# Buttons.net
KiCad netlist of a schematic drawn in Altium Designer
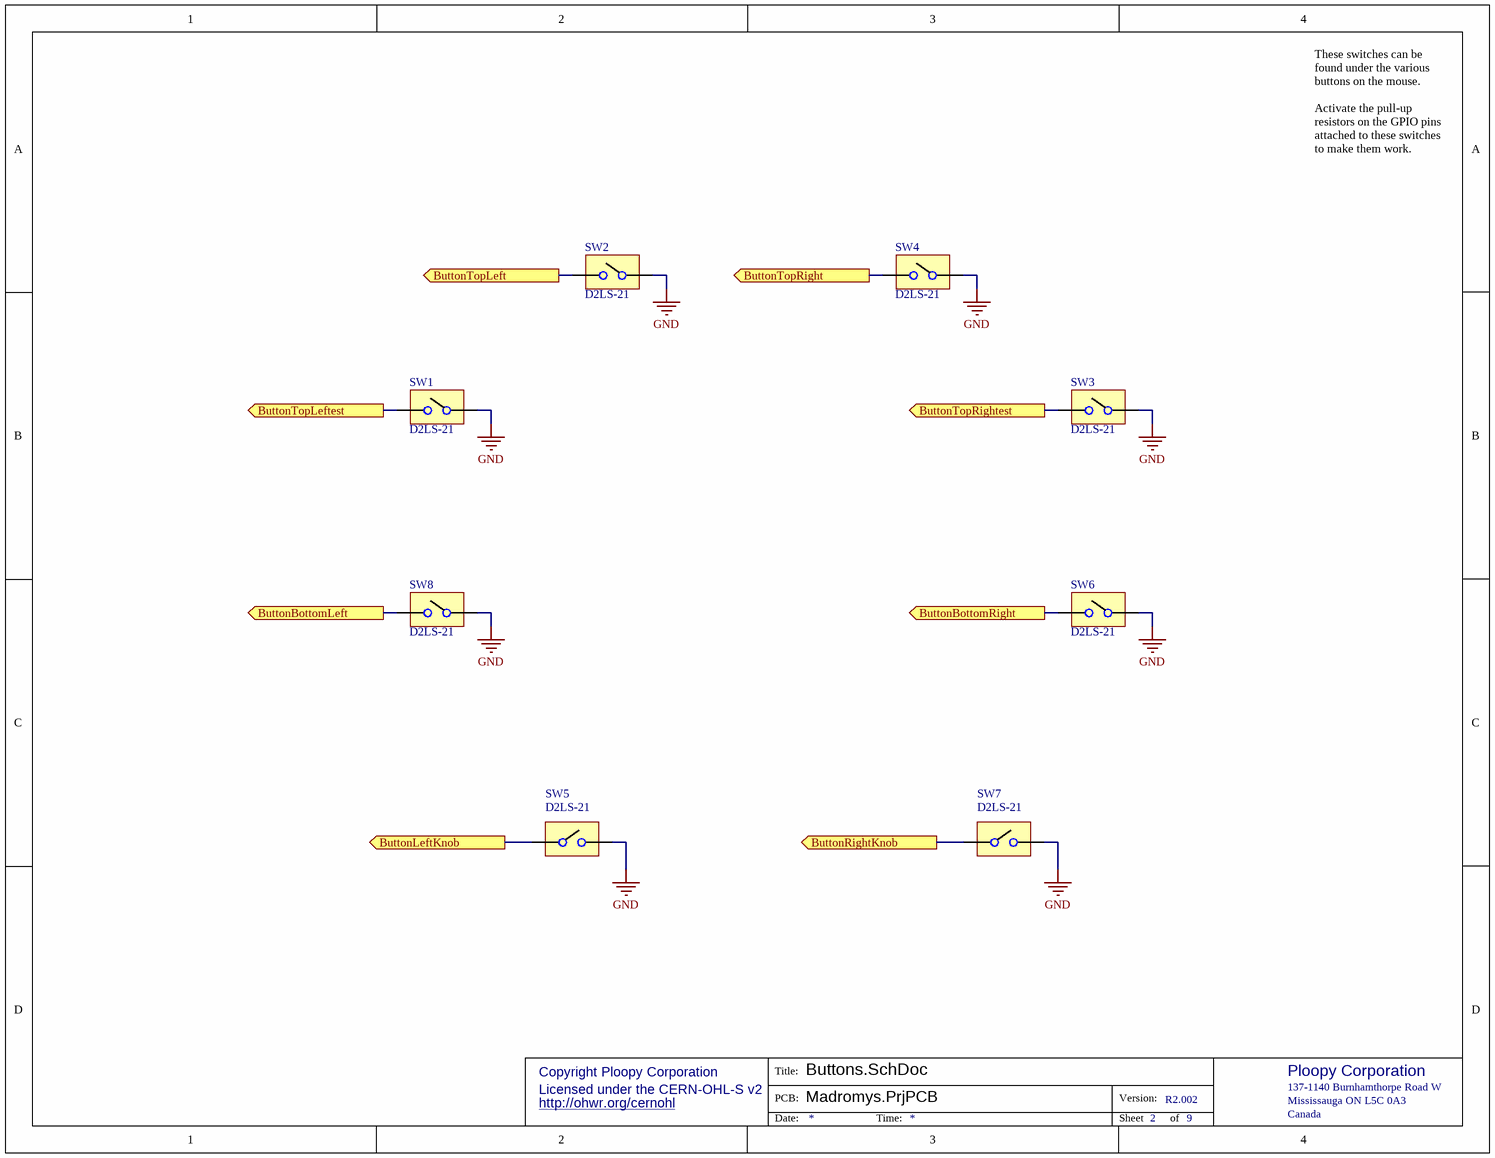
[diagram p0: Buttons.SchDoc]

(export (version "E")
  (design (tool "Eeschema 10.0.6"))
  (components
    (comp (ref "SW1")
      (value "D2LS-21")
      (footprint "D2LS-21")
      (description "Compact Surface-mounting Switch for long durability")
      (libsource (lib "Switches") (part "D2LS-21"))
    )
    (comp (ref "SW2")
      (value "D2LS-21")
      (footprint "D2LS-21")
      (description "Compact Surface-mounting Switch for long durability")
      (libsource (lib "Switches") (part "D2LS-21"))
    )
    (comp (ref "SW3")
      (value "D2LS-21")
      (footprint "D2LS-21")
      (description "Compact Surface-mounting Switch for long durability")
      (libsource (lib "Switches") (part "D2LS-21"))
    )
    (comp (ref "SW4")
      (value "D2LS-21")
      (footprint "D2LS-21")
      (description "Compact Surface-mounting Switch for long durability")
      (libsource (lib "Switches") (part "D2LS-21"))
    )
    (comp (ref "SW5")
      (value "D2LS-21")
      (footprint "D2LS-21")
      (description "Compact Surface-mounting Switch for long durability")
      (libsource (lib "") (part "D2LS-21_1"))
    )
    (comp (ref "SW6")
      (value "D2LS-21")
      (footprint "D2LS-21")
      (description "Compact Surface-mounting Switch for long durability")
      (libsource (lib "Switches") (part "D2LS-21"))
    )
    (comp (ref "SW7")
      (value "D2LS-21")
      (footprint "D2LS-21")
      (description "Compact Surface-mounting Switch for long durability")
      (libsource (lib "") (part "D2LS-21_1"))
    )
    (comp (ref "SW8")
      (value "D2LS-21")
      (footprint "D2LS-21")
      (description "Compact Surface-mounting Switch for long durability")
      (libsource (lib "Switches") (part "D2LS-21"))
    )
  )
  (nets
    (net (code "1") (name "/ButtonBottomLeft") (class "Default")
      (node (ref "SW8") (pin "B") (pinfunction "B_B") (pintype "passive"))
    )
    (net (code "2") (name "/ButtonBottomRight") (class "Default")
      (node (ref "SW6") (pin "B") (pinfunction "B_B") (pintype "passive"))
    )
    (net (code "3") (name "/ButtonLeftKnob") (class "Default")
      (node (ref "SW5") (pin "A") (pinfunction "A_A") (pintype "passive"))
    )
    (net (code "4") (name "/ButtonRightKnob") (class "Default")
      (node (ref "SW7") (pin "A") (pinfunction "A_A") (pintype "passive"))
    )
    (net (code "5") (name "/ButtonTopLeft") (class "Default")
      (node (ref "SW2") (pin "B") (pinfunction "B_B") (pintype "passive"))
    )
    (net (code "6") (name "/ButtonTopLeftest") (class "Default")
      (node (ref "SW1") (pin "B") (pinfunction "B_B") (pintype "passive"))
    )
    (net (code "7") (name "/ButtonTopRight") (class "Default")
      (node (ref "SW4") (pin "B") (pinfunction "B_B") (pintype "passive"))
    )
    (net (code "8") (name "/ButtonTopRightest") (class "Default")
      (node (ref "SW3") (pin "B") (pinfunction "B_B") (pintype "passive"))
    )
    (net (code "9") (name "GND") (class "Default")
      (node (ref "SW1") (pin "A") (pinfunction "A_A") (pintype "passive"))
      (node (ref "SW2") (pin "A") (pinfunction "A_A") (pintype "passive"))
      (node (ref "SW3") (pin "A") (pinfunction "A_A") (pintype "passive"))
      (node (ref "SW4") (pin "A") (pinfunction "A_A") (pintype "passive"))
      (node (ref "SW5") (pin "B") (pinfunction "B_B") (pintype "passive"))
      (node (ref "SW6") (pin "A") (pinfunction "A_A") (pintype "passive"))
      (node (ref "SW7") (pin "B") (pinfunction "B_B") (pintype "passive"))
      (node (ref "SW8") (pin "A") (pinfunction "A_A") (pintype "passive"))
    )
  )
)
